# driver1.net
KiCad netlist of a schematic drawn in EAGLE
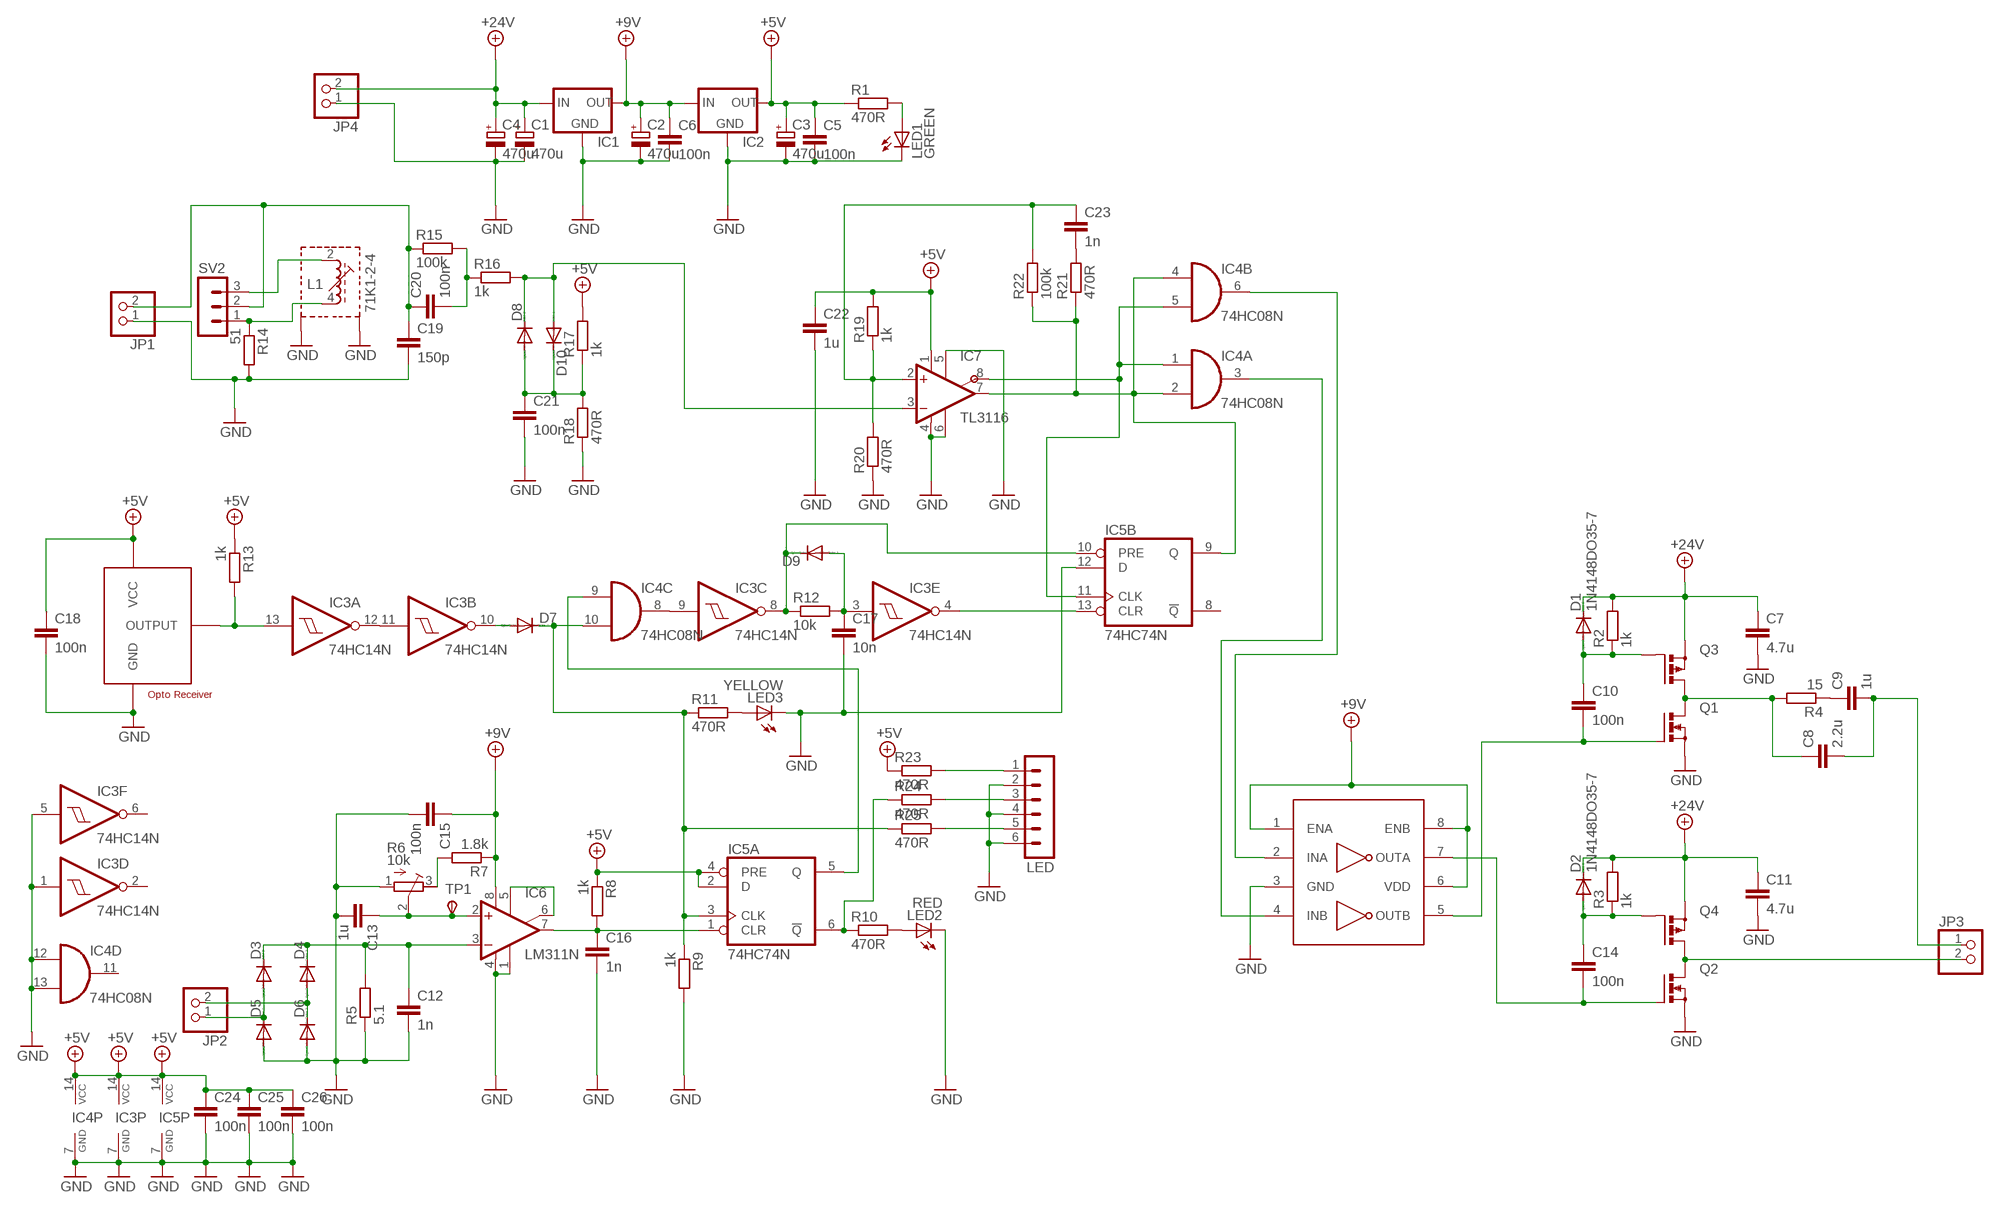
[diagram p0: schematic, sheet 1]

(export (version "E")
  (design (tool "Eeschema 10.0.6"))
  (components
    (comp (ref "C1")
      (value "470u")
      (footprint "eagle-import:E5-8,5")
      (libsource (lib "eagle-import") (part "CPOL-EUE5-8.5"))
    )
    (comp (ref "C2")
      (value "470u")
      (footprint "eagle-import:E5-8,5")
      (libsource (lib "eagle-import") (part "CPOL-EUE5-8.5"))
    )
    (comp (ref "C3")
      (value "470u")
      (footprint "eagle-import:E5-8,5")
      (libsource (lib "eagle-import") (part "CPOL-EUE5-8.5"))
    )
    (comp (ref "C4")
      (value "470u")
      (footprint "eagle-import:E5-8,5")
      (libsource (lib "eagle-import") (part "CPOL-EUE5-8.5"))
    )
    (comp (ref "C5")
      (value "100n")
      (footprint "eagle-import:C025-025X050")
      (libsource (lib "eagle-import") (part "C-EU025-025X050"))
    )
    (comp (ref "C6")
      (value "100n")
      (footprint "eagle-import:C025-025X050")
      (libsource (lib "eagle-import") (part "C-EU025-025X050"))
    )
    (comp (ref "C7")
      (value "4.7u")
      (footprint "eagle-import:C025-025X050")
      (libsource (lib "eagle-import") (part "C-EU025-025X050"))
    )
    (comp (ref "C8")
      (value "2.2u")
      (footprint "eagle-import:C025-025X050")
      (libsource (lib "eagle-import") (part "C-EU025-025X050"))
    )
    (comp (ref "C9")
      (value "1u")
      (footprint "eagle-import:C025-025X050")
      (libsource (lib "eagle-import") (part "C-EU025-025X050"))
    )
    (comp (ref "C10")
      (value "100n")
      (footprint "eagle-import:C025-025X050")
      (libsource (lib "eagle-import") (part "C-EU025-025X050"))
    )
    (comp (ref "C11")
      (value "4.7u")
      (footprint "eagle-import:C025-025X050")
      (libsource (lib "eagle-import") (part "C-EU025-025X050"))
    )
    (comp (ref "C12")
      (value "1n")
      (footprint "eagle-import:C025-025X050")
      (libsource (lib "eagle-import") (part "C-EU025-025X050"))
    )
    (comp (ref "C13")
      (value "1u")
      (footprint "eagle-import:C025-025X050")
      (libsource (lib "eagle-import") (part "C-EU025-025X050"))
    )
    (comp (ref "C14")
      (value "100n")
      (footprint "eagle-import:C025-025X050")
      (libsource (lib "eagle-import") (part "C-EU025-025X050"))
    )
    (comp (ref "C15")
      (value "100n")
      (footprint "eagle-import:C025-025X050")
      (libsource (lib "eagle-import") (part "C-EU025-025X050"))
    )
    (comp (ref "C16")
      (value "1n")
      (footprint "eagle-import:C025-025X050")
      (libsource (lib "eagle-import") (part "C-EU025-025X050"))
    )
    (comp (ref "C17")
      (value "10n")
      (footprint "eagle-import:C025-025X050")
      (libsource (lib "eagle-import") (part "C-EU025-025X050"))
    )
    (comp (ref "C18")
      (value "100n")
      (footprint "eagle-import:C025-025X050")
      (libsource (lib "eagle-import") (part "C-EU025-025X050"))
    )
    (comp (ref "C19")
      (value "150p")
      (footprint "eagle-import:C025-025X050")
      (libsource (lib "eagle-import") (part "C-EU025-025X050"))
    )
    (comp (ref "C20")
      (value "100n")
      (footprint "eagle-import:C025-025X050")
      (libsource (lib "eagle-import") (part "C-EU025-025X050"))
    )
    (comp (ref "C21")
      (value "100n")
      (footprint "eagle-import:C025-025X050")
      (libsource (lib "eagle-import") (part "C-EU025-025X050"))
    )
    (comp (ref "C22")
      (value "1u")
      (footprint "eagle-import:C025-025X050")
      (libsource (lib "eagle-import") (part "C-EU025-025X050"))
    )
    (comp (ref "C23")
      (value "1n")
      (footprint "eagle-import:C025-025X050")
      (libsource (lib "eagle-import") (part "C-EU025-025X050"))
    )
    (comp (ref "C24")
      (value "100n")
      (footprint "eagle-import:C025-025X050")
      (libsource (lib "eagle-import") (part "C-EU025-025X050"))
    )
    (comp (ref "C25")
      (value "100n")
      (footprint "eagle-import:C025-025X050")
      (libsource (lib "eagle-import") (part "C-EU025-025X050"))
    )
    (comp (ref "C26")
      (value "100n")
      (footprint "eagle-import:C025-025X050")
      (libsource (lib "eagle-import") (part "C-EU025-025X050"))
    )
    (comp (ref "D1")
      (value "1N4148DO35-7")
      (footprint "eagle-import:DO35-7")
      (libsource (lib "eagle-import") (part "1N4148DO35-7"))
    )
    (comp (ref "D2")
      (value "1N4148DO35-7")
      (footprint "eagle-import:DO35-7")
      (libsource (lib "eagle-import") (part "1N4148DO35-7"))
    )
    (comp (ref "D3")
      (value "DIODE-D-7.5")
      (footprint "eagle-import:D-7.5")
      (libsource (lib "eagle-import") (part "DIODE-D-7.5"))
    )
    (comp (ref "D4")
      (value "DIODE-D-7.5")
      (footprint "eagle-import:D-7.5")
      (libsource (lib "eagle-import") (part "DIODE-D-7.5"))
    )
    (comp (ref "D5")
      (value "DIODE-D-7.5")
      (footprint "eagle-import:D-7.5")
      (libsource (lib "eagle-import") (part "DIODE-D-7.5"))
    )
    (comp (ref "D6")
      (value "DIODE-D-7.5")
      (footprint "eagle-import:D-7.5")
      (libsource (lib "eagle-import") (part "DIODE-D-7.5"))
    )
    (comp (ref "D7")
      (value "DIODE-D-7.5")
      (footprint "eagle-import:D-7.5")
      (libsource (lib "eagle-import") (part "DIODE-D-7.5"))
    )
    (comp (ref "D8")
      (value "DIODE-D-7.5")
      (footprint "eagle-import:D-7.5")
      (libsource (lib "eagle-import") (part "DIODE-D-7.5"))
    )
    (comp (ref "D9")
      (value "DIODE-D-7.5")
      (footprint "eagle-import:D-7.5")
      (libsource (lib "eagle-import") (part "DIODE-D-7.5"))
    )
    (comp (ref "D10")
      (value "DIODE-D-7.5")
      (footprint "eagle-import:D-7.5")
      (libsource (lib "eagle-import") (part "DIODE-D-7.5"))
    )
    (comp (ref "IC1")
      (value "78XXS")
      (footprint "eagle-import:78XXS")
      (libsource (lib "eagle-import") (part "78XXS"))
    )
    (comp (ref "IC2")
      (value "78XXS")
      (footprint "eagle-import:78XXS")
      (libsource (lib "eagle-import") (part "78XXS"))
    )
    (comp (ref "IC3")
      (value "74HC14N")
      (footprint "eagle-import:DIL14")
      (libsource (lib "eagle-import") (part "7414NHC"))
    )
    (comp (ref "IC4")
      (value "74HC08N")
      (footprint "eagle-import:DIL14")
      (libsource (lib "eagle-import") (part "7408NHC"))
    )
    (comp (ref "IC5")
      (value "74HC74N")
      (footprint "eagle-import:DIL14")
      (libsource (lib "eagle-import") (part "7474NHC"))
    )
    (comp (ref "IC6")
      (value "LM311N")
      (footprint "eagle-import:DIL8")
      (libsource (lib "eagle-import") (part "LM311N"))
    )
    (comp (ref "IC7")
      (value "TL3116")
      (footprint "eagle-import:DIL8")
      (libsource (lib "eagle-import") (part "TL3116"))
    )
    (comp (ref "IC8")
      (value "UCC27423")
      (footprint "eagle-import:DIL8")
      (libsource (lib "eagle-import") (part "UCC27423"))
    )
    (comp (ref "JP1")
      (value "PINHD-1X2")
      (footprint "eagle-import:1X02")
      (libsource (lib "eagle-import") (part "PINHD-1X2"))
    )
    (comp (ref "JP2")
      (value "PINHD-1X2")
      (footprint "eagle-import:1X02")
      (libsource (lib "eagle-import") (part "PINHD-1X2"))
    )
    (comp (ref "JP3")
      (value "PINHD-1X2")
      (footprint "eagle-import:1X02")
      (libsource (lib "eagle-import") (part "PINHD-1X2"))
    )
    (comp (ref "JP4")
      (value "PINHD-1X2")
      (footprint "eagle-import:1X02")
      (libsource (lib "eagle-import") (part "PINHD-1X2"))
    )
    (comp (ref "L1")
      (value "71K1-2-4")
      (footprint "eagle-import:71K")
      (libsource (lib "eagle-import") (part "71K1-2-4"))
    )
    (comp (ref "LED")
      (value "MA06-1")
      (footprint "eagle-import:MA06-1")
      (libsource (lib "eagle-import") (part "MA06-1"))
    )
    (comp (ref "LED1")
      (value "GREEN")
      (footprint "eagle-import:LED3MM")
      (libsource (lib "eagle-import") (part "LED3MM"))
    )
    (comp (ref "LED2")
      (value "RED")
      (footprint "eagle-import:LED3MM")
      (libsource (lib "eagle-import") (part "LED3MM"))
    )
    (comp (ref "LED3")
      (value "YELLOW")
      (footprint "eagle-import:LED3MM")
      (libsource (lib "eagle-import") (part "LED3MM"))
    )
    (comp (ref "OP1")
      (value "IFD95")
      (footprint "eagle-import:OPTO-RECEIVER")
      (libsource (lib "eagle-import") (part "IFD95"))
    )
    (comp (ref "Q1")
      (value "PMOSFET_NTO220BV")
      (footprint "eagle-import:TO220BV")
      (libsource (lib "eagle-import") (part "PMOSFET_NTO220BV"))
    )
    (comp (ref "Q2")
      (value "PMOSFET_NTO220BV")
      (footprint "eagle-import:TO220BV")
      (libsource (lib "eagle-import") (part "PMOSFET_NTO220BV"))
    )
    (comp (ref "Q3")
      (value "PMOSFET_PTO220BV")
      (footprint "eagle-import:TO220BV")
      (libsource (lib "eagle-import") (part "PMOSFET_PTO220BV"))
    )
    (comp (ref "Q4")
      (value "PMOSFET_PTO220BV")
      (footprint "eagle-import:TO220BV")
      (libsource (lib "eagle-import") (part "PMOSFET_PTO220BV"))
    )
    (comp (ref "R1")
      (value "470R")
      (footprint "eagle-import:0207_7")
      (libsource (lib "eagle-import") (part "R-EU_0207/7"))
    )
    (comp (ref "R2")
      (value "1k")
      (footprint "eagle-import:0207_7")
      (libsource (lib "eagle-import") (part "R-EU_0207/7"))
    )
    (comp (ref "R3")
      (value "1k")
      (footprint "eagle-import:0207_7")
      (libsource (lib "eagle-import") (part "R-EU_0207/7"))
    )
    (comp (ref "R4")
      (value "15")
      (footprint "eagle-import:0207_7")
      (libsource (lib "eagle-import") (part "R-EU_0207/7"))
    )
    (comp (ref "R5")
      (value "5.1")
      (footprint "eagle-import:0309_12")
      (libsource (lib "eagle-import") (part "R-EU_0309/12"))
    )
    (comp (ref "R6")
      (value "10k")
      (footprint "eagle-import:RTRIM64W")
      (libsource (lib "eagle-import") (part "R-TRIMM64W"))
    )
    (comp (ref "R7")
      (value "1.8k")
      (footprint "eagle-import:0207_7")
      (libsource (lib "eagle-import") (part "R-EU_0207/7"))
    )
    (comp (ref "R8")
      (value "1k")
      (footprint "eagle-import:0207_7")
      (libsource (lib "eagle-import") (part "R-EU_0207/7"))
    )
    (comp (ref "R9")
      (value "1k")
      (footprint "eagle-import:0207_7")
      (libsource (lib "eagle-import") (part "R-EU_0207/7"))
    )
    (comp (ref "R10")
      (value "470R")
      (footprint "eagle-import:0207_7")
      (libsource (lib "eagle-import") (part "R-EU_0207/7"))
    )
    (comp (ref "R11")
      (value "470R")
      (footprint "eagle-import:0207_7")
      (libsource (lib "eagle-import") (part "R-EU_0207/7"))
    )
    (comp (ref "R12")
      (value "10k")
      (footprint "eagle-import:0207_7")
      (libsource (lib "eagle-import") (part "R-EU_0207/7"))
    )
    (comp (ref "R13")
      (value "1k")
      (footprint "eagle-import:0207_7")
      (libsource (lib "eagle-import") (part "R-EU_0207/7"))
    )
    (comp (ref "R14")
      (value "51")
      (footprint "eagle-import:0309_12")
      (libsource (lib "eagle-import") (part "R-EU_0309/12"))
    )
    (comp (ref "R15")
      (value "100k")
      (footprint "eagle-import:0207_7")
      (libsource (lib "eagle-import") (part "R-EU_0207/7"))
    )
    (comp (ref "R16")
      (value "1k")
      (footprint "eagle-import:0207_7")
      (libsource (lib "eagle-import") (part "R-EU_0207/7"))
    )
    (comp (ref "R17")
      (value "1k")
      (footprint "eagle-import:0207_7")
      (libsource (lib "eagle-import") (part "R-EU_0207/7"))
    )
    (comp (ref "R18")
      (value "470R")
      (footprint "eagle-import:0207_7")
      (libsource (lib "eagle-import") (part "R-EU_0207/7"))
    )
    (comp (ref "R19")
      (value "1k")
      (footprint "eagle-import:0207_7")
      (libsource (lib "eagle-import") (part "R-EU_0207/7"))
    )
    (comp (ref "R20")
      (value "470R")
      (footprint "eagle-import:0207_7")
      (libsource (lib "eagle-import") (part "R-EU_0207/7"))
    )
    (comp (ref "R21")
      (value "470R")
      (footprint "eagle-import:0207_7")
      (libsource (lib "eagle-import") (part "R-EU_0207/7"))
    )
    (comp (ref "R22")
      (value "100k")
      (footprint "eagle-import:0207_7")
      (libsource (lib "eagle-import") (part "R-EU_0207/7"))
    )
    (comp (ref "R23")
      (value "470R")
      (footprint "eagle-import:0207_7")
      (libsource (lib "eagle-import") (part "R-EU_0207/7"))
    )
    (comp (ref "R24")
      (value "470R")
      (footprint "eagle-import:0207_7")
      (libsource (lib "eagle-import") (part "R-EU_0207/7"))
    )
    (comp (ref "R25")
      (value "470R")
      (footprint "eagle-import:0207_7")
      (libsource (lib "eagle-import") (part "R-EU_0207/7"))
    )
    (comp (ref "SV2")
      (value "MA03-1")
      (footprint "eagle-import:MA03-1")
      (libsource (lib "eagle-import") (part "MA03-1"))
    )
    (comp (ref "TP1")
      (value "TPSTP20R")
      (footprint "eagle-import:TP20R")
      (libsource (lib "eagle-import") (part "TPSTP20R"))
    )
  )
  (nets
    (net (code "1") (name "+5V") (class "Default")
      (node (ref "C18") (pin "1") (pinfunction "1_1") (pintype "passive"))
      (node (ref "C22") (pin "1") (pinfunction "1_1") (pintype "passive"))
      (node (ref "C24") (pin "1") (pinfunction "1_1") (pintype "passive"))
      (node (ref "C25") (pin "1") (pinfunction "1_1") (pintype "passive"))
      (node (ref "C26") (pin "1") (pinfunction "1_1") (pintype "passive"))
      (node (ref "C3") (pin "+") (pinfunction "+_+") (pintype "passive"))
      (node (ref "C5") (pin "1") (pinfunction "1_1") (pintype "passive"))
      (node (ref "IC2") (pin "OUT") (pinfunction "OUT_OUT") (pintype "passive"))
      (node (ref "IC3") (pin "14") (pinfunction "VCC_14") (pintype "power_in"))
      (node (ref "IC4") (pin "14") (pinfunction "VCC_14") (pintype "power_in"))
      (node (ref "IC5") (pin "14") (pinfunction "VCC_14") (pintype "power_in"))
      (node (ref "IC5") (pin "2") (pinfunction "D_2") (pintype "input"))
      (node (ref "IC5") (pin "4") (pinfunction "PRE_4") (pintype "input"))
      (node (ref "IC7") (pin "1") (pinfunction "V+_1") (pintype "power_in"))
      (node (ref "OP1") (pin "P$3") (pinfunction "VCC_P$3") (pintype "power_in"))
      (node (ref "R1") (pin "1") (pinfunction "1_1") (pintype "passive"))
      (node (ref "R13") (pin "1") (pinfunction "1_1") (pintype "passive"))
      (node (ref "R17") (pin "2") (pinfunction "2_2") (pintype "passive"))
      (node (ref "R19") (pin "2") (pinfunction "2_2") (pintype "passive"))
      (node (ref "R23") (pin "1") (pinfunction "1_1") (pintype "passive"))
      (node (ref "R8") (pin "1") (pinfunction "1_1") (pintype "passive"))
    )
    (net (code "2") (name "+9V") (class "Default")
      (node (ref "C15") (pin "1") (pinfunction "1_1") (pintype "passive"))
      (node (ref "C2") (pin "+") (pinfunction "+_+") (pintype "passive"))
      (node (ref "C6") (pin "1") (pinfunction "1_1") (pintype "passive"))
      (node (ref "IC1") (pin "OUT") (pinfunction "OUT_OUT") (pintype "passive"))
      (node (ref "IC2") (pin "IN") (pinfunction "IN_IN") (pintype "input"))
      (node (ref "IC6") (pin "8") (pinfunction "V+_8") (pintype "power_in"))
      (node (ref "IC8") (pin "1") (pinfunction "ENA_1") (pintype "bidirectional"))
      (node (ref "IC8") (pin "6") (pinfunction "VDD_6") (pintype "bidirectional"))
      (node (ref "IC8") (pin "8") (pinfunction "ENB_8") (pintype "bidirectional"))
      (node (ref "R7") (pin "1") (pinfunction "1_1") (pintype "passive"))
    )
    (net (code "3") (name "+24V") (class "Default")
      (node (ref "C1") (pin "+") (pinfunction "+_+") (pintype "passive"))
      (node (ref "C11") (pin "1") (pinfunction "1_1") (pintype "passive"))
      (node (ref "C4") (pin "+") (pinfunction "+_+") (pintype "passive"))
      (node (ref "C7") (pin "1") (pinfunction "1_1") (pintype "passive"))
      (node (ref "D1") (pin "C") (pinfunction "C_C") (pintype "passive"))
      (node (ref "D2") (pin "C") (pinfunction "C_C") (pintype "passive"))
      (node (ref "IC1") (pin "IN") (pinfunction "IN_IN") (pintype "input"))
      (node (ref "JP4") (pin "2") (pinfunction "2_2") (pintype "passive"))
      (node (ref "Q3") (pin "S") (pinfunction "S_S") (pintype "passive"))
      (node (ref "Q4") (pin "S") (pinfunction "S_S") (pintype "passive"))
      (node (ref "R2") (pin "2") (pinfunction "2_2") (pintype "passive"))
      (node (ref "R3") (pin "2") (pinfunction "2_2") (pintype "passive"))
    )
    (net (code "4") (name "GND") (class "Default")
      (node (ref "C1") (pin "-") (pinfunction "-_-") (pintype "passive"))
      (node (ref "C11") (pin "2") (pinfunction "2_2") (pintype "passive"))
      (node (ref "C12") (pin "2") (pinfunction "2_2") (pintype "passive"))
      (node (ref "C13") (pin "2") (pinfunction "2_2") (pintype "passive"))
      (node (ref "C15") (pin "2") (pinfunction "2_2") (pintype "passive"))
      (node (ref "C16") (pin "2") (pinfunction "2_2") (pintype "passive"))
      (node (ref "C17") (pin "2") (pinfunction "2_2") (pintype "passive"))
      (node (ref "C18") (pin "2") (pinfunction "2_2") (pintype "passive"))
      (node (ref "C19") (pin "2") (pinfunction "2_2") (pintype "passive"))
      (node (ref "C2") (pin "-") (pinfunction "-_-") (pintype "passive"))
      (node (ref "C21") (pin "2") (pinfunction "2_2") (pintype "passive"))
      (node (ref "C22") (pin "2") (pinfunction "2_2") (pintype "passive"))
      (node (ref "C24") (pin "2") (pinfunction "2_2") (pintype "passive"))
      (node (ref "C25") (pin "2") (pinfunction "2_2") (pintype "passive"))
      (node (ref "C26") (pin "2") (pinfunction "2_2") (pintype "passive"))
      (node (ref "C3") (pin "-") (pinfunction "-_-") (pintype "passive"))
      (node (ref "C4") (pin "-") (pinfunction "-_-") (pintype "passive"))
      (node (ref "C5") (pin "2") (pinfunction "2_2") (pintype "passive"))
      (node (ref "C6") (pin "2") (pinfunction "2_2") (pintype "passive"))
      (node (ref "C7") (pin "2") (pinfunction "2_2") (pintype "passive"))
      (node (ref "D5") (pin "A") (pinfunction "A_A") (pintype "passive"))
      (node (ref "D6") (pin "A") (pinfunction "A_A") (pintype "passive"))
      (node (ref "IC1") (pin "GND") (pinfunction "GND_GND") (pintype "input"))
      (node (ref "IC2") (pin "GND") (pinfunction "GND_GND") (pintype "input"))
      (node (ref "IC3") (pin "1") (pinfunction "I_1") (pintype "input"))
      (node (ref "IC3") (pin "5") (pinfunction "I_5") (pintype "input"))
      (node (ref "IC3") (pin "7") (pinfunction "GND_7") (pintype "power_in"))
      (node (ref "IC4") (pin "12") (pinfunction "I0_12") (pintype "input"))
      (node (ref "IC4") (pin "13") (pinfunction "I1_13") (pintype "input"))
      (node (ref "IC4") (pin "7") (pinfunction "GND_7") (pintype "power_in"))
      (node (ref "IC5") (pin "12") (pinfunction "D_12") (pintype "input"))
      (node (ref "IC5") (pin "7") (pinfunction "GND_7") (pintype "power_in"))
      (node (ref "IC6") (pin "1") (pinfunction "GND_1") (pintype "passive"))
      (node (ref "IC6") (pin "4") (pinfunction "V-_4") (pintype "power_in"))
      (node (ref "IC7") (pin "4") (pinfunction "V-_4") (pintype "power_in"))
      (node (ref "IC7") (pin "5") (pinfunction "LEN_5") (pintype "passive"))
      (node (ref "IC7") (pin "6") (pinfunction "GND_6") (pintype "passive"))
      (node (ref "IC8") (pin "3") (pinfunction "GND_3") (pintype "bidirectional"))
      (node (ref "JP1") (pin "1") (pinfunction "1_1") (pintype "passive"))
      (node (ref "JP4") (pin "1") (pinfunction "1_1") (pintype "passive"))
      (node (ref "L1") (pin "S1") (pinfunction "S1_S1") (pintype "passive"))
      (node (ref "L1") (pin "S2") (pinfunction "S2_S2") (pintype "passive"))
      (node (ref "LED") (pin "2") (pinfunction "2_2") (pintype "passive"))
      (node (ref "LED") (pin "4") (pinfunction "4_4") (pintype "passive"))
      (node (ref "LED") (pin "6") (pinfunction "6_6") (pintype "passive"))
      (node (ref "LED1") (pin "K") (pinfunction "C_K") (pintype "passive"))
      (node (ref "LED2") (pin "K") (pinfunction "C_K") (pintype "passive"))
      (node (ref "LED3") (pin "K") (pinfunction "C_K") (pintype "passive"))
      (node (ref "OP1") (pin "P$1") (pinfunction "GND_P$1") (pintype "power_in"))
      (node (ref "Q1") (pin "S") (pinfunction "S_S") (pintype "passive"))
      (node (ref "Q2") (pin "S") (pinfunction "S_S") (pintype "passive"))
      (node (ref "R14") (pin "2") (pinfunction "2_2") (pintype "passive"))
      (node (ref "R18") (pin "1") (pinfunction "1_1") (pintype "passive"))
      (node (ref "R20") (pin "1") (pinfunction "1_1") (pintype "passive"))
      (node (ref "R5") (pin "1") (pinfunction "1_1") (pintype "passive"))
      (node (ref "R6") (pin "1") (pinfunction "A_1") (pintype "passive"))
      (node (ref "R9") (pin "2") (pinfunction "2_2") (pintype "passive"))
    )
    (net (code "5") (name "Net-(C8-Pad1)") (class "Default")
      (node (ref "C8") (pin "1") (pinfunction "1_1") (pintype "passive"))
      (node (ref "Q1") (pin "D") (pinfunction "D_D") (pintype "passive"))
      (node (ref "Q3") (pin "D") (pinfunction "D_D") (pintype "passive"))
      (node (ref "R4") (pin "2") (pinfunction "2_2") (pintype "passive"))
    )
    (net (code "6") (name "Net-(C8-Pad2)") (class "Default")
      (node (ref "C8") (pin "2") (pinfunction "2_2") (pintype "passive"))
      (node (ref "C9") (pin "2") (pinfunction "2_2") (pintype "passive"))
      (node (ref "JP3") (pin "1") (pinfunction "1_1") (pintype "passive"))
    )
    (net (code "7") (name "Net-(C9-Pad1)") (class "Default")
      (node (ref "C9") (pin "1") (pinfunction "1_1") (pintype "passive"))
      (node (ref "R4") (pin "1") (pinfunction "1_1") (pintype "passive"))
    )
    (net (code "8") (name "Net-(C10-Pad1)") (class "Default")
      (node (ref "C10") (pin "1") (pinfunction "1_1") (pintype "passive"))
      (node (ref "D1") (pin "A") (pinfunction "A_A") (pintype "passive"))
      (node (ref "Q3") (pin "G") (pinfunction "G_G") (pintype "passive"))
      (node (ref "R2") (pin "1") (pinfunction "1_1") (pintype "passive"))
    )
    (net (code "9") (name "Net-(C14-Pad1)") (class "Default")
      (node (ref "C14") (pin "1") (pinfunction "1_1") (pintype "passive"))
      (node (ref "D2") (pin "A") (pinfunction "A_A") (pintype "passive"))
      (node (ref "Q4") (pin "G") (pinfunction "G_G") (pintype "passive"))
      (node (ref "R3") (pin "1") (pinfunction "1_1") (pintype "passive"))
    )
    (net (code "10") (name "Net-(C19-Pad1)") (class "Default")
      (node (ref "C19") (pin "1") (pinfunction "1_1") (pintype "passive"))
      (node (ref "C20") (pin "1") (pinfunction "1_1") (pintype "passive"))
      (node (ref "JP1") (pin "2") (pinfunction "2_2") (pintype "passive"))
      (node (ref "R15") (pin "1") (pinfunction "1_1") (pintype "passive"))
      (node (ref "SV2") (pin "2") (pinfunction "2_2") (pintype "passive"))
    )
    (net (code "11") (name "Net-(C20-Pad2)") (class "Default")
      (node (ref "C20") (pin "2") (pinfunction "2_2") (pintype "passive"))
      (node (ref "R15") (pin "2") (pinfunction "2_2") (pintype "passive"))
      (node (ref "R16") (pin "1") (pinfunction "1_1") (pintype "passive"))
    )
    (net (code "12") (name "Net-(C21-Pad1)") (class "Default")
      (node (ref "C21") (pin "1") (pinfunction "1_1") (pintype "passive"))
      (node (ref "D10") (pin "C") (pinfunction "C_C") (pintype "passive"))
      (node (ref "D8") (pin "A") (pinfunction "A_A") (pintype "passive"))
      (node (ref "R17") (pin "1") (pinfunction "1_1") (pintype "passive"))
      (node (ref "R18") (pin "2") (pinfunction "2_2") (pintype "passive"))
    )
    (net (code "13") (name "Net-(C23-Pad2)") (class "Default")
      (node (ref "C23") (pin "2") (pinfunction "2_2") (pintype "passive"))
      (node (ref "R21") (pin "2") (pinfunction "2_2") (pintype "passive"))
    )
    (net (code "14") (name "Net-(D3-PadA)") (class "Default")
      (node (ref "D3") (pin "A") (pinfunction "A_A") (pintype "passive"))
      (node (ref "D5") (pin "C") (pinfunction "C_C") (pintype "passive"))
      (node (ref "JP2") (pin "1") (pinfunction "1_1") (pintype "passive"))
    )
    (net (code "15") (name "Net-(D4-PadA)") (class "Default")
      (node (ref "D4") (pin "A") (pinfunction "A_A") (pintype "passive"))
      (node (ref "D6") (pin "C") (pinfunction "C_C") (pintype "passive"))
      (node (ref "JP2") (pin "2") (pinfunction "2_2") (pintype "passive"))
    )
    (net (code "16") (name "Net-(IC3A-I)") (class "Default")
      (node (ref "IC3") (pin "13") (pinfunction "I_13") (pintype "input"))
      (node (ref "OP1") (pin "P$2") (pinfunction "OUTPUT_P$2") (pintype "output"))
      (node (ref "R13") (pin "2") (pinfunction "2_2") (pintype "passive"))
    )
    (net (code "17") (name "Net-(IC3A-O)") (class "Default")
      (node (ref "IC3") (pin "11") (pinfunction "I_11") (pintype "input"))
      (node (ref "IC3") (pin "12") (pinfunction "O_12") (pintype "output"))
    )
    (net (code "18") (name "Net-(IC3B-O)") (class "Default")
      (node (ref "D7") (pin "A") (pinfunction "A_A") (pintype "passive"))
      (node (ref "IC3") (pin "10") (pinfunction "O_10") (pintype "output"))
    )
    (net (code "19") (name "Net-(IC3C-I)") (class "Default")
      (node (ref "IC3") (pin "9") (pinfunction "I_9") (pintype "input"))
      (node (ref "IC4") (pin "8") (pinfunction "O_8") (pintype "output"))
    )
    (net (code "20") (name "Net-(IC3C-O)") (class "Default")
      (node (ref "D9") (pin "C") (pinfunction "C_C") (pintype "passive"))
      (node (ref "IC3") (pin "8") (pinfunction "O_8") (pintype "output"))
      (node (ref "IC5") (pin "10") (pinfunction "PRE_10") (pintype "input"))
      (node (ref "R12") (pin "1") (pinfunction "1_1") (pintype "passive"))
    )
    (net (code "21") (name "Net-(IC3E-I)") (class "Default")
      (node (ref "C17") (pin "1") (pinfunction "1_1") (pintype "passive"))
      (node (ref "D9") (pin "A") (pinfunction "A_A") (pintype "passive"))
      (node (ref "IC3") (pin "3") (pinfunction "I_3") (pintype "input"))
      (node (ref "R12") (pin "2") (pinfunction "2_2") (pintype "passive"))
    )
    (net (code "22") (name "Net-(IC3E-O)") (class "Default")
      (node (ref "IC3") (pin "4") (pinfunction "O_4") (pintype "output"))
      (node (ref "IC5") (pin "13") (pinfunction "CLR_13") (pintype "input"))
    )
    (net (code "23") (name "Net-(IC4A-I0)") (class "Default")
      (node (ref "IC4") (pin "1") (pinfunction "I0_1") (pintype "input"))
      (node (ref "IC4") (pin "5") (pinfunction "I1_5") (pintype "input"))
      (node (ref "IC5") (pin "11") (pinfunction "CLK_11") (pintype "input"))
      (node (ref "IC7") (pin "8") (pinfunction "~{OUT}_8") (pintype "passive"))
    )
    (net (code "24") (name "Net-(IC4A-I1)") (class "Default")
      (node (ref "IC4") (pin "2") (pinfunction "I1_2") (pintype "input"))
      (node (ref "IC4") (pin "4") (pinfunction "I0_4") (pintype "input"))
      (node (ref "IC5") (pin "9") (pinfunction "Q_9") (pintype "output"))
      (node (ref "IC7") (pin "7") (pinfunction "OUT_7") (pintype "output"))
      (node (ref "R21") (pin "1") (pinfunction "1_1") (pintype "passive"))
      (node (ref "R22") (pin "1") (pinfunction "1_1") (pintype "passive"))
    )
    (net (code "25") (name "Net-(IC4A-O)") (class "Default")
      (node (ref "IC4") (pin "3") (pinfunction "O_3") (pintype "output"))
      (node (ref "IC8") (pin "4") (pinfunction "INB_4") (pintype "bidirectional"))
    )
    (net (code "26") (name "Net-(IC4B-O)") (class "Default")
      (node (ref "IC4") (pin "6") (pinfunction "O_6") (pintype "output"))
      (node (ref "IC8") (pin "2") (pinfunction "INA_2") (pintype "bidirectional"))
    )
    (net (code "27") (name "Net-(IC4C-I0)") (class "Default")
      (node (ref "IC4") (pin "9") (pinfunction "I0_9") (pintype "input"))
      (node (ref "IC5") (pin "5") (pinfunction "Q_5") (pintype "output"))
    )
    (net (code "28") (name "Net-(IC4C-I1)") (class "Default")
      (node (ref "D7") (pin "C") (pinfunction "C_C") (pintype "passive"))
      (node (ref "IC4") (pin "10") (pinfunction "I1_10") (pintype "input"))
      (node (ref "IC5") (pin "3") (pinfunction "CLK_3") (pintype "input"))
      (node (ref "R11") (pin "1") (pinfunction "1_1") (pintype "passive"))
      (node (ref "R25") (pin "1") (pinfunction "1_1") (pintype "passive"))
      (node (ref "R9") (pin "1") (pinfunction "1_1") (pintype "passive"))
    )
    (net (code "29") (name "Net-(IC5A-CLR)") (class "Default")
      (node (ref "C16") (pin "1") (pinfunction "1_1") (pintype "passive"))
      (node (ref "IC5") (pin "1") (pinfunction "CLR_1") (pintype "input"))
      (node (ref "IC6") (pin "7") (pinfunction "OUT_7") (pintype "output"))
      (node (ref "R8") (pin "2") (pinfunction "2_2") (pintype "passive"))
    )
    (net (code "30") (name "Net-(IC5A-~{Q})") (class "Default")
      (node (ref "IC5") (pin "6") (pinfunction "~{Q}_6") (pintype "output"))
      (node (ref "R10") (pin "1") (pinfunction "1_1") (pintype "passive"))
      (node (ref "R24") (pin "1") (pinfunction "1_1") (pintype "passive"))
    )
    (net (code "31") (name "Net-(IC6-+IN)") (class "Default")
      (node (ref "C13") (pin "1") (pinfunction "1_1") (pintype "passive"))
      (node (ref "IC6") (pin "2") (pinfunction "+IN_2") (pintype "input"))
      (node (ref "R6") (pin "2") (pinfunction "S_2") (pintype "passive"))
      (node (ref "TP1") (pin "TP") (pinfunction "PP_TP") (pintype "input"))
    )
    (net (code "32") (name "Net-(IC6--IN)") (class "Default")
      (node (ref "C12") (pin "1") (pinfunction "1_1") (pintype "passive"))
      (node (ref "D3") (pin "C") (pinfunction "C_C") (pintype "passive"))
      (node (ref "D4") (pin "C") (pinfunction "C_C") (pintype "passive"))
      (node (ref "IC6") (pin "3") (pinfunction "-IN_3") (pintype "input"))
      (node (ref "R5") (pin "2") (pinfunction "2_2") (pintype "passive"))
    )
    (net (code "33") (name "Net-(IC6-ON)") (class "Default")
      (node (ref "IC6") (pin "5") (pinfunction "ON_5") (pintype "passive"))
      (node (ref "IC6") (pin "6") (pinfunction "ON/STR_6") (pintype "passive"))
    )
    (net (code "34") (name "Net-(IC7-+IN)") (class "Default")
      (node (ref "C23") (pin "1") (pinfunction "1_1") (pintype "passive"))
      (node (ref "IC7") (pin "2") (pinfunction "+IN_2") (pintype "input"))
      (node (ref "R19") (pin "1") (pinfunction "1_1") (pintype "passive"))
      (node (ref "R20") (pin "2") (pinfunction "2_2") (pintype "passive"))
      (node (ref "R22") (pin "2") (pinfunction "2_2") (pintype "passive"))
    )
    (net (code "35") (name "Net-(IC7--IN)") (class "Default")
      (node (ref "D10") (pin "A") (pinfunction "A_A") (pintype "passive"))
      (node (ref "D8") (pin "C") (pinfunction "C_C") (pintype "passive"))
      (node (ref "IC7") (pin "3") (pinfunction "-IN_3") (pintype "input"))
      (node (ref "R16") (pin "2") (pinfunction "2_2") (pintype "passive"))
    )
    (net (code "36") (name "Net-(IC8-OUTA)") (class "Default")
      (node (ref "C14") (pin "2") (pinfunction "2_2") (pintype "passive"))
      (node (ref "IC8") (pin "7") (pinfunction "OUTA_7") (pintype "bidirectional"))
      (node (ref "Q2") (pin "G") (pinfunction "G_G") (pintype "passive"))
    )
    (net (code "37") (name "Net-(IC8-OUTB)") (class "Default")
      (node (ref "C10") (pin "2") (pinfunction "2_2") (pintype "passive"))
      (node (ref "IC8") (pin "5") (pinfunction "OUTB_5") (pintype "bidirectional"))
      (node (ref "Q1") (pin "G") (pinfunction "G_G") (pintype "passive"))
    )
    (net (code "38") (name "Net-(JP3-Pad2)") (class "Default")
      (node (ref "JP3") (pin "2") (pinfunction "2_2") (pintype "passive"))
      (node (ref "Q2") (pin "D") (pinfunction "D_D") (pintype "passive"))
      (node (ref "Q4") (pin "D") (pinfunction "D_D") (pintype "passive"))
    )
    (net (code "39") (name "Net-(L1A-A)") (class "Default")
      (node (ref "L1") (pin "2") (pinfunction "A_2") (pintype "passive"))
      (node (ref "SV2") (pin "3") (pinfunction "3_3") (pintype "passive"))
    )
    (net (code "40") (name "Net-(L1A-E)") (class "Default")
      (node (ref "L1") (pin "4") (pinfunction "E_4") (pintype "passive"))
      (node (ref "R14") (pin "1") (pinfunction "1_1") (pintype "passive"))
      (node (ref "SV2") (pin "1") (pinfunction "1_1") (pintype "passive"))
    )
    (net (code "41") (name "Net-(LED-Pad1)") (class "Default")
      (node (ref "LED") (pin "1") (pinfunction "1_1") (pintype "passive"))
      (node (ref "R23") (pin "2") (pinfunction "2_2") (pintype "passive"))
    )
    (net (code "42") (name "Net-(LED-Pad3)") (class "Default")
      (node (ref "LED") (pin "3") (pinfunction "3_3") (pintype "passive"))
      (node (ref "R24") (pin "2") (pinfunction "2_2") (pintype "passive"))
    )
    (net (code "43") (name "Net-(LED-Pad5)") (class "Default")
      (node (ref "LED") (pin "5") (pinfunction "5_5") (pintype "passive"))
      (node (ref "R25") (pin "2") (pinfunction "2_2") (pintype "passive"))
    )
    (net (code "44") (name "Net-(LED1-PadA)") (class "Default")
      (node (ref "LED1") (pin "A") (pinfunction "A_A") (pintype "passive"))
      (node (ref "R1") (pin "2") (pinfunction "2_2") (pintype "passive"))
    )
    (net (code "45") (name "Net-(LED2-PadA)") (class "Default")
      (node (ref "LED2") (pin "A") (pinfunction "A_A") (pintype "passive"))
      (node (ref "R10") (pin "2") (pinfunction "2_2") (pintype "passive"))
    )
    (net (code "46") (name "Net-(LED3-PadA)") (class "Default")
      (node (ref "LED3") (pin "A") (pinfunction "A_A") (pintype "passive"))
      (node (ref "R11") (pin "2") (pinfunction "2_2") (pintype "passive"))
    )
    (net (code "47") (name "Net-(R6-E)") (class "Default")
      (node (ref "R6") (pin "3") (pinfunction "E_3") (pintype "passive"))
      (node (ref "R7") (pin "2") (pinfunction "2_2") (pintype "passive"))
    )
    (net (code "48") (name "unconnected-(IC3D-O-Pad2)") (class "Default")
      (node (ref "IC3") (pin "2") (pinfunction "O_2") (pintype "output"))
    )
    (net (code "49") (name "unconnected-(IC3F-O-Pad6)") (class "Default")
      (node (ref "IC3") (pin "6") (pinfunction "O_6") (pintype "output"))
    )
    (net (code "50") (name "unconnected-(IC4D-O-Pad11)") (class "Default")
      (node (ref "IC4") (pin "11") (pinfunction "O_11") (pintype "output"))
    )
    (net (code "51") (name "unconnected-(IC5B-~{Q}-Pad8)") (class "Default")
      (node (ref "IC5") (pin "8") (pinfunction "~{Q}_8") (pintype "output"))
    )
  )
)
